# design.net
KiCad netlist of a schematic drawn in EAGLE
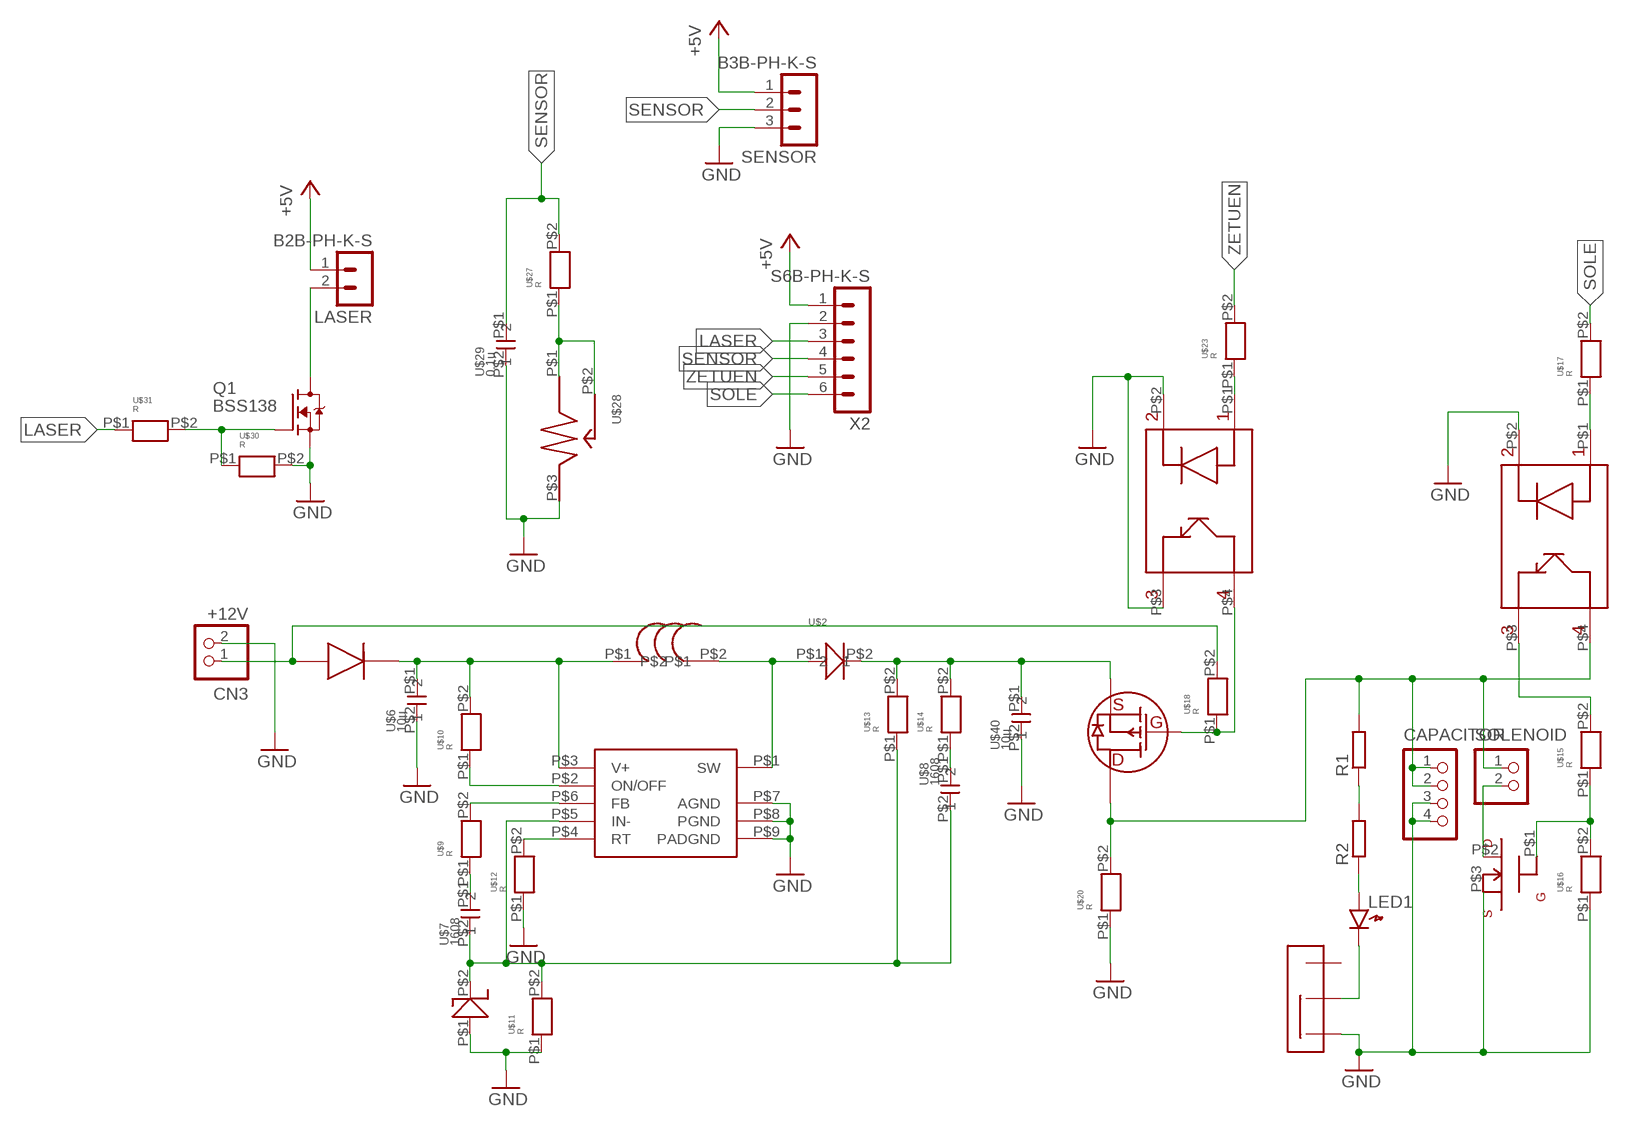
[diagram p0: schematic, sheet 1]
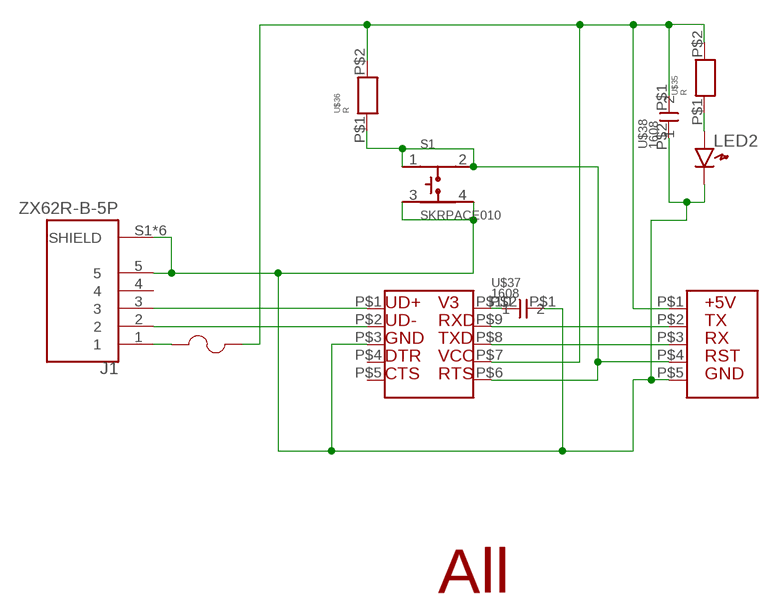
[diagram p1: schematic, sheet 2]

(export (version "E")
  (design (tool "Eeschema 10.0.6"))
  (components
    (comp (ref "CAPACITOR")
      (value "B4B-XH-A")
      (footprint "eagle-import:B4B-XH-A")
      (libsource (lib "eagle-import") (part "B4B-XH-A"))
    )
    (comp (ref "CN3")
      (value "+12V")
      (footprint "eagle-import:B2B-XH-A")
      (libsource (lib "eagle-import") (part "B2B-XH-A"))
    )
    (comp (ref "LASER")
      (value "B2B-PH-K-S")
      (footprint "eagle-import:B2B-PH-K-S")
      (libsource (lib "eagle-import") (part "B2B-PH-K-S"))
    )
    (comp (ref "LED1")
      (value "LED1608")
      (footprint "eagle-import:LED1608")
      (libsource (lib "eagle-import") (part "LED1608"))
    )
    (comp (ref "Q1")
      (value "BSS138")
      (footprint "eagle-import:SOT23")
      (fields (field (name "MF") "Fairchild"))
      (libsource (lib "eagle-import") (part "BSS138"))
    )
    (comp (ref "R1")
      (value "R-EU_0207/10")
      (footprint "eagle-import:0207_10")
      (libsource (lib "eagle-import") (part "R-EU_0207/10"))
    )
    (comp (ref "R2")
      (value "R-EU_0207/10")
      (footprint "eagle-import:0207_10")
      (libsource (lib "eagle-import") (part "R-EU_0207/10"))
    )
    (comp (ref "SENSOR")
      (value "B3B-PH-K-S")
      (footprint "eagle-import:B3B-PH-K-S")
      (libsource (lib "eagle-import") (part "B3B-PH-K-S"))
    )
    (comp (ref "SOLENOID")
      (value "B2B-XH-A")
      (footprint "eagle-import:B2B-XH-A")
      (libsource (lib "eagle-import") (part "B2B-XH-A"))
    )
    (comp (ref "U$1") (value "TD") (footprint "eagle-import:TD") (libsource (lib "eagle-import") (part "TD")))
    (comp (ref "U$2") (value "D") (footprint "eagle-import:D") (libsource (lib "eagle-import") (part "D")))
    (comp (ref "U$3")
      (value "40V5A")
      (footprint "eagle-import:40V5A")
      (libsource (lib "eagle-import") (part "40V5A"))
    )
    (comp (ref "U$4") (value "I") (footprint "eagle-import:I") (libsource (lib "eagle-import") (part "I")))
    (comp (ref "U$5")
      (value "NJW4131GM1")
      (footprint "eagle-import:NJW4131")
      (libsource (lib "eagle-import") (part "NJW4131GM1"))
    )
    (comp (ref "U$6")
      (value "10u")
      (footprint "eagle-import:CON")
      (libsource (lib "eagle-import") (part "1608"))
    )
    (comp (ref "U$7")
      (value "1608")
      (footprint "eagle-import:CON")
      (libsource (lib "eagle-import") (part "1608"))
    )
    (comp (ref "U$8")
      (value "1608")
      (footprint "eagle-import:CON")
      (libsource (lib "eagle-import") (part "1608"))
    )
    (comp (ref "U$9") (value "R") (footprint "eagle-import:1608") (libsource (lib "eagle-import") (part "R")))
    (comp (ref "U$10")
      (value "R")
      (footprint "eagle-import:1608")
      (libsource (lib "eagle-import") (part "R"))
    )
    (comp (ref "U$11")
      (value "R")
      (footprint "eagle-import:1608")
      (libsource (lib "eagle-import") (part "R"))
    )
    (comp (ref "U$12")
      (value "R")
      (footprint "eagle-import:1608")
      (libsource (lib "eagle-import") (part "R"))
    )
    (comp (ref "U$13")
      (value "R")
      (footprint "eagle-import:1608")
      (libsource (lib "eagle-import") (part "R"))
    )
    (comp (ref "U$14")
      (value "R")
      (footprint "eagle-import:1608")
      (libsource (lib "eagle-import") (part "R"))
    )
    (comp (ref "U$15")
      (value "R")
      (footprint "eagle-import:1608")
      (libsource (lib "eagle-import") (part "R"))
    )
    (comp (ref "U$16")
      (value "R")
      (footprint "eagle-import:1608")
      (libsource (lib "eagle-import") (part "R"))
    )
    (comp (ref "U$17")
      (value "R")
      (footprint "eagle-import:1608")
      (libsource (lib "eagle-import") (part "R"))
    )
    (comp (ref "U$18")
      (value "R")
      (footprint "eagle-import:1608")
      (libsource (lib "eagle-import") (part "R"))
    )
    (comp (ref "U$20")
      (value "R")
      (footprint "eagle-import:1608")
      (libsource (lib "eagle-import") (part "R"))
    )
    (comp (ref "U$21")
      (value "MOS")
      (footprint "eagle-import:MOS")
      (libsource (lib "eagle-import") (part "MOS"))
    )
    (comp (ref "U$22")
      (value "PMOSPMOS")
      (footprint "eagle-import:PMOS")
      (libsource (lib "eagle-import") (part "PMOSPMOS"))
    )
    (comp (ref "U$23")
      (value "R")
      (footprint "eagle-import:1608")
      (libsource (lib "eagle-import") (part "R"))
    )
    (comp (ref "U$24")
      (value "TLP291")
      (footprint "eagle-import:TPL291")
      (libsource (lib "eagle-import") (part "TLP291"))
    )
    (comp (ref "U$25")
      (value "TLP291")
      (footprint "eagle-import:TPL291")
      (libsource (lib "eagle-import") (part "TLP291"))
    )
    (comp (ref "U$26")
      (value "SSW")
      (footprint "eagle-import:SSW")
      (libsource (lib "eagle-import") (part "SSW"))
    )
    (comp (ref "U$27")
      (value "R")
      (footprint "eagle-import:1608")
      (libsource (lib "eagle-import") (part "R"))
    )
    (comp (ref "U$28")
      (value "VR")
      (footprint "eagle-import:VR")
      (libsource (lib "eagle-import") (part "VR"))
    )
    (comp (ref "U$29")
      (value "0.1u")
      (footprint "eagle-import:CON")
      (libsource (lib "eagle-import") (part "1608"))
    )
    (comp (ref "U$30")
      (value "R")
      (footprint "eagle-import:1608")
      (libsource (lib "eagle-import") (part "R"))
    )
    (comp (ref "U$31")
      (value "R")
      (footprint "eagle-import:1608")
      (libsource (lib "eagle-import") (part "R"))
    )
    (comp (ref "U$40")
      (value "10u")
      (footprint "eagle-import:CON")
      (libsource (lib "eagle-import") (part "1608"))
    )
    (comp (ref "X2")
      (value "S6B-PH-K-S")
      (footprint "eagle-import:S6B-PH-K-S")
      (libsource (lib "eagle-import") (part "S6B-PH-K-S"))
    )
    (comp (ref "J1")
      (value "ZX62R-B-5P")
      (footprint "eagle-import:HRS_ZX62R-B-5P")
      (fields (field (name "MF") "Hirose"))
      (libsource (lib "eagle-import") (part "ZX62R-B-5P"))
    )
    (comp (ref "LED2")
      (value "LED1608")
      (footprint "eagle-import:LED1608")
      (libsource (lib "eagle-import") (part "LED1608"))
    )
    (comp (ref "S1")
      (value "SKRPACE010")
      (footprint "eagle-import:SW_SKRPACE010")
      (fields (field (name "MF") "ALPS"))
      (libsource (lib "eagle-import") (part "SKRPACE010"))
    )
    (comp (ref "U$32")
      (value "CH340K")
      (footprint "eagle-import:CH340K")
      (libsource (lib "eagle-import") (part "CH340K"))
    )
    (comp (ref "U$33") (value "F") (footprint "eagle-import:F") (libsource (lib "eagle-import") (part "F")))
    (comp (ref "U$34")
      (value "SI")
      (footprint "eagle-import:SI")
      (libsource (lib "eagle-import") (part "SI"))
    )
    (comp (ref "U$35")
      (value "R")
      (footprint "eagle-import:1608")
      (libsource (lib "eagle-import") (part "R"))
    )
    (comp (ref "U$36")
      (value "R")
      (footprint "eagle-import:1608")
      (libsource (lib "eagle-import") (part "R"))
    )
    (comp (ref "U$37")
      (value "1608")
      (footprint "eagle-import:CON")
      (libsource (lib "eagle-import") (part "1608"))
    )
    (comp (ref "U$38")
      (value "1608")
      (footprint "eagle-import:CON")
      (libsource (lib "eagle-import") (part "1608"))
    )
    (comp (ref "U$39")
      (value "ALL")
      (footprint "eagle-import:ALL")
      (libsource (lib "eagle-import") (part "ALL"))
    )
  )
  (nets
    (net (code "1") (name "+5V") (class "Default")
      (node (ref "LASER") (pin "1") (pinfunction "1_1") (pintype "passive"))
      (node (ref "SENSOR") (pin "1") (pinfunction "1_1") (pintype "passive"))
      (node (ref "X2") (pin "1") (pinfunction "1_1") (pintype "passive"))
    )
    (net (code "2") (name "GND") (class "Default")
      (node (ref "CAPACITOR") (pin "3") (pinfunction "3_3") (pintype "passive"))
      (node (ref "CAPACITOR") (pin "4") (pinfunction "4_4") (pintype "passive"))
      (node (ref "CN3") (pin "2") (pinfunction "2_2") (pintype "passive"))
      (node (ref "Q1") (pin "2") (pinfunction "S_2") (pintype "passive"))
      (node (ref "SENSOR") (pin "3") (pinfunction "3_3") (pintype "passive"))
      (node (ref "U$1") (pin "P$1") (pinfunction "P$1_P$1") (pintype "bidirectional"))
      (node (ref "U$11") (pin "P$1") (pinfunction "P$1_P$1") (pintype "bidirectional"))
      (node (ref "U$12") (pin "P$1") (pinfunction "P$1_P$1") (pintype "bidirectional"))
      (node (ref "U$16") (pin "P$1") (pinfunction "P$1_P$1") (pintype "bidirectional"))
      (node (ref "U$20") (pin "P$1") (pinfunction "P$1_P$1") (pintype "bidirectional"))
      (node (ref "U$21") (pin "P$3") (pinfunction "P$2_P$3") (pintype "bidirectional"))
      (node (ref "U$24") (pin "P$2") (pinfunction "2_P$2") (pintype "bidirectional"))
      (node (ref "U$24") (pin "P$3") (pinfunction "3_P$3") (pintype "bidirectional"))
      (node (ref "U$25") (pin "P$2") (pinfunction "2_P$2") (pintype "bidirectional"))
      (node (ref "U$26") (pin "P$1") (pinfunction "P$1_P$1") (pintype "bidirectional"))
      (node (ref "U$28") (pin "P$3") (pinfunction "P$3_P$3") (pintype "bidirectional"))
      (node (ref "U$29") (pin "P$2") (pinfunction "2_P$2") (pintype "bidirectional"))
      (node (ref "U$30") (pin "P$2") (pinfunction "P$2_P$2") (pintype "bidirectional"))
      (node (ref "U$40") (pin "P$2") (pinfunction "2_P$2") (pintype "bidirectional"))
      (node (ref "U$5") (pin "P$7") (pinfunction "AGND_P$7") (pintype "bidirectional"))
      (node (ref "U$5") (pin "P$8") (pinfunction "PGND_P$8") (pintype "bidirectional"))
      (node (ref "U$5") (pin "P$9") (pinfunction "PADGND_P$9") (pintype "bidirectional"))
      (node (ref "U$6") (pin "P$2") (pinfunction "2_P$2") (pintype "bidirectional"))
      (node (ref "X2") (pin "2") (pinfunction "2_2") (pintype "passive"))
    )
    (net (code "3") (name "LASER") (class "Default")
      (node (ref "U$31") (pin "P$1") (pinfunction "P$1_P$1") (pintype "bidirectional"))
      (node (ref "X2") (pin "3") (pinfunction "3_3") (pintype "passive"))
    )
    (net (code "4") (name "Net-(CN3-Pad1)") (class "Default")
      (node (ref "CN3") (pin "1") (pinfunction "1_1") (pintype "passive"))
      (node (ref "U$18") (pin "P$2") (pinfunction "P$2_P$2") (pintype "bidirectional"))
      (node (ref "U$3") (pin "P$1") (pinfunction "P$1_P$1") (pintype "bidirectional"))
    )
    (net (code "5") (name "Net-(J1-Pad1)") (class "Default")
      (node (ref "J1") (pin "1") (pinfunction "1_1") (pintype "passive"))
      (node (ref "U$33") (pin "P$2") (pinfunction "P$2_P$2") (pintype "bidirectional"))
    )
    (net (code "6") (name "Net-(J1-Pad2)") (class "Default")
      (node (ref "J1") (pin "2") (pinfunction "2_2") (pintype "passive"))
      (node (ref "U$32") (pin "P$2") (pinfunction "P$2_P$2") (pintype "bidirectional"))
    )
    (net (code "7") (name "Net-(J1-Pad3)") (class "Default")
      (node (ref "J1") (pin "3") (pinfunction "3_3") (pintype "passive"))
      (node (ref "U$32") (pin "P$1") (pinfunction "P$1_P$1") (pintype "bidirectional"))
    )
    (net (code "8") (name "Net-(LED1-PadA)") (class "Default")
      (node (ref "LED1") (pin "A") (pinfunction "A_A") (pintype "passive"))
      (node (ref "R2") (pin "1") (pinfunction "1_1") (pintype "passive"))
    )
    (net (code "9") (name "Net-(LED2-PadA)") (class "Default")
      (node (ref "LED2") (pin "A") (pinfunction "A_A") (pintype "passive"))
      (node (ref "U$35") (pin "P$1") (pinfunction "P$1_P$1") (pintype "bidirectional"))
    )
    (net (code "10") (name "Net-(Q1-D)") (class "Default")
      (node (ref "LASER") (pin "2") (pinfunction "2_2") (pintype "passive"))
      (node (ref "Q1") (pin "3") (pinfunction "D_3") (pintype "passive"))
    )
    (net (code "11") (name "Net-(Q1-G)") (class "Default")
      (node (ref "Q1") (pin "1") (pinfunction "G_1") (pintype "passive"))
      (node (ref "U$30") (pin "P$1") (pinfunction "P$1_P$1") (pintype "bidirectional"))
      (node (ref "U$31") (pin "P$2") (pinfunction "P$2_P$2") (pintype "bidirectional"))
    )
    (net (code "12") (name "Net-(R1-Pad1)") (class "Default")
      (node (ref "R1") (pin "1") (pinfunction "1_1") (pintype "passive"))
      (node (ref "R2") (pin "2") (pinfunction "2_2") (pintype "passive"))
    )
    (net (code "13") (name "Net-(S1-Pad1)") (class "Default")
      (node (ref "S1") (pin "1") (pinfunction "1_1") (pintype "bidirectional"))
      (node (ref "S1") (pin "2") (pinfunction "2_2") (pintype "bidirectional"))
      (node (ref "U$32") (pin "P$6") (pinfunction "P$6_P$6") (pintype "bidirectional"))
      (node (ref "U$34") (pin "P$4") (pinfunction "P$4_P$4") (pintype "bidirectional"))
      (node (ref "U$36") (pin "P$1") (pinfunction "P$1_P$1") (pintype "bidirectional"))
    )
    (net (code "14") (name "Net-(U$2-1)") (class "Default")
      (node (ref "U$2") (pin "P$1") (pinfunction "1_P$1") (pintype "bidirectional"))
      (node (ref "U$4") (pin "P$2") (pinfunction "P$2_P$2") (pintype "bidirectional"))
      (node (ref "U$5") (pin "P$1") (pinfunction "SW_P$1") (pintype "bidirectional"))
    )
    (net (code "15") (name "Net-(U$2-2)") (class "Default")
      (node (ref "U$13") (pin "P$2") (pinfunction "P$2_P$2") (pintype "bidirectional"))
      (node (ref "U$14") (pin "P$2") (pinfunction "P$2_P$2") (pintype "bidirectional"))
      (node (ref "U$2") (pin "P$2") (pinfunction "2_P$2") (pintype "bidirectional"))
      (node (ref "U$22") (pin "S") (pinfunction "S_S") (pintype "bidirectional"))
      (node (ref "U$40") (pin "P$1") (pinfunction "1_P$1") (pintype "bidirectional"))
    )
    (net (code "16") (name "Net-(U$5-FB)") (class "Default")
      (node (ref "U$5") (pin "P$6") (pinfunction "FB_P$6") (pintype "bidirectional"))
      (node (ref "U$9") (pin "P$2") (pinfunction "P$2_P$2") (pintype "bidirectional"))
    )
    (net (code "17") (name "Net-(U$5-IN-)") (class "Default")
      (node (ref "U$1") (pin "P$2") (pinfunction "P$2_P$2") (pintype "bidirectional"))
      (node (ref "U$11") (pin "P$2") (pinfunction "P$2_P$2") (pintype "bidirectional"))
      (node (ref "U$13") (pin "P$1") (pinfunction "P$1_P$1") (pintype "bidirectional"))
      (node (ref "U$5") (pin "P$5") (pinfunction "IN-_P$5") (pintype "bidirectional"))
      (node (ref "U$7") (pin "P$2") (pinfunction "2_P$2") (pintype "bidirectional"))
      (node (ref "U$8") (pin "P$2") (pinfunction "2_P$2") (pintype "bidirectional"))
    )
    (net (code "18") (name "Net-(U$5-ON{slash}OFF)") (class "Default")
      (node (ref "U$10") (pin "P$1") (pinfunction "P$1_P$1") (pintype "bidirectional"))
      (node (ref "U$5") (pin "P$2") (pinfunction "ON/OFF_P$2") (pintype "bidirectional"))
    )
    (net (code "19") (name "Net-(U$5-RT)") (class "Default")
      (node (ref "U$12") (pin "P$2") (pinfunction "P$2_P$2") (pintype "bidirectional"))
      (node (ref "U$5") (pin "P$4") (pinfunction "RT_P$4") (pintype "bidirectional"))
    )
    (net (code "20") (name "Net-(U$5-V+)") (class "Default")
      (node (ref "U$10") (pin "P$2") (pinfunction "P$2_P$2") (pintype "bidirectional"))
      (node (ref "U$3") (pin "P$2") (pinfunction "P$2_P$2") (pintype "bidirectional"))
      (node (ref "U$4") (pin "P$1") (pinfunction "P$1_P$1") (pintype "bidirectional"))
      (node (ref "U$5") (pin "P$3") (pinfunction "V+_P$3") (pintype "bidirectional"))
      (node (ref "U$6") (pin "P$1") (pinfunction "1_P$1") (pintype "bidirectional"))
    )
    (net (code "21") (name "Net-(U$7-1)") (class "Default")
      (node (ref "U$7") (pin "P$1") (pinfunction "1_P$1") (pintype "bidirectional"))
      (node (ref "U$9") (pin "P$1") (pinfunction "P$1_P$1") (pintype "bidirectional"))
    )
    (net (code "22") (name "Net-(U$8-1)") (class "Default")
      (node (ref "U$14") (pin "P$1") (pinfunction "P$1_P$1") (pintype "bidirectional"))
      (node (ref "U$8") (pin "P$1") (pinfunction "1_P$1") (pintype "bidirectional"))
    )
    (net (code "23") (name "Net-(U$21-P$1)") (class "Default")
      (node (ref "SOLENOID") (pin "2") (pinfunction "2_2") (pintype "passive"))
      (node (ref "U$21") (pin "P$2") (pinfunction "P$1_P$2") (pintype "bidirectional"))
    )
    (net (code "24") (name "Net-(U$21-P$3)") (class "Default")
      (node (ref "U$15") (pin "P$1") (pinfunction "P$1_P$1") (pintype "bidirectional"))
      (node (ref "U$16") (pin "P$2") (pinfunction "P$2_P$2") (pintype "bidirectional"))
      (node (ref "U$21") (pin "P$1") (pinfunction "P$3_P$1") (pintype "bidirectional"))
    )
    (net (code "25") (name "Net-(U$24-1)") (class "Default")
      (node (ref "U$23") (pin "P$1") (pinfunction "P$1_P$1") (pintype "bidirectional"))
      (node (ref "U$24") (pin "P$1") (pinfunction "1_P$1") (pintype "bidirectional"))
    )
    (net (code "26") (name "Net-(U$24-4)") (class "Default")
      (node (ref "U$18") (pin "P$1") (pinfunction "P$1_P$1") (pintype "bidirectional"))
      (node (ref "U$22") (pin "G") (pinfunction "G_G") (pintype "bidirectional"))
      (node (ref "U$24") (pin "P$4") (pinfunction "4_P$4") (pintype "bidirectional"))
    )
    (net (code "27") (name "Net-(U$25-1)") (class "Default")
      (node (ref "U$17") (pin "P$1") (pinfunction "P$1_P$1") (pintype "bidirectional"))
      (node (ref "U$25") (pin "P$1") (pinfunction "1_P$1") (pintype "bidirectional"))
    )
    (net (code "28") (name "Net-(U$25-3)") (class "Default")
      (node (ref "U$15") (pin "P$2") (pinfunction "P$2_P$2") (pintype "bidirectional"))
      (node (ref "U$25") (pin "P$3") (pinfunction "3_P$3") (pintype "bidirectional"))
    )
    (net (code "29") (name "Net-(U$25-4)") (class "Default")
      (node (ref "CAPACITOR") (pin "1") (pinfunction "1_1") (pintype "passive"))
      (node (ref "CAPACITOR") (pin "2") (pinfunction "2_2") (pintype "passive"))
      (node (ref "R1") (pin "2") (pinfunction "2_2") (pintype "passive"))
      (node (ref "SOLENOID") (pin "1") (pinfunction "1_1") (pintype "passive"))
      (node (ref "U$20") (pin "P$2") (pinfunction "P$2_P$2") (pintype "bidirectional"))
      (node (ref "U$22") (pin "D") (pinfunction "D_D") (pintype "bidirectional"))
      (node (ref "U$25") (pin "P$4") (pinfunction "4_P$4") (pintype "bidirectional"))
    )
    (net (code "30") (name "Net-(U$26-P$2)") (class "Default")
      (node (ref "LED1") (pin "K") (pinfunction "K_K") (pintype "passive"))
      (node (ref "U$26") (pin "P$3") (pinfunction "P$2_P$3") (pintype "bidirectional"))
    )
    (net (code "31") (name "Net-(U$27-PadP$1)") (class "Default")
      (node (ref "U$27") (pin "P$1") (pinfunction "P$1_P$1") (pintype "bidirectional"))
      (node (ref "U$28") (pin "P$1") (pinfunction "P$1_P$1") (pintype "bidirectional"))
      (node (ref "U$28") (pin "P$2") (pinfunction "P$2_P$2") (pintype "bidirectional"))
    )
    (net (code "32") (name "Net-(U$32-PadP$8)") (class "Default")
      (node (ref "U$32") (pin "P$8") (pinfunction "P$8_P$8") (pintype "bidirectional"))
      (node (ref "U$34") (pin "P$3") (pinfunction "P$3_P$3") (pintype "bidirectional"))
    )
    (net (code "33") (name "Net-(U$32-PadP$9)") (class "Default")
      (node (ref "U$32") (pin "P$9") (pinfunction "P$9_P$9") (pintype "bidirectional"))
      (node (ref "U$34") (pin "P$2") (pinfunction "P$2_P$2") (pintype "bidirectional"))
    )
    (net (code "34") (name "Net-(U$37-1)") (class "Default")
      (node (ref "J1") (pin "5") (pinfunction "5_5") (pintype "passive"))
      (node (ref "J1") (pin "S1") (pinfunction "SHIELD_S1") (pintype "passive"))
      (node (ref "J1") (pin "S2") (pinfunction "SHIELD_S2") (pintype "passive"))
      (node (ref "J1") (pin "S3") (pinfunction "SHIELD_S3") (pintype "passive"))
      (node (ref "J1") (pin "S4") (pinfunction "SHIELD_S4") (pintype "passive"))
      (node (ref "J1") (pin "S5") (pinfunction "SHIELD_S5") (pintype "passive"))
      (node (ref "J1") (pin "S6") (pinfunction "SHIELD_S6") (pintype "passive"))
      (node (ref "LED2") (pin "K") (pinfunction "K_K") (pintype "passive"))
      (node (ref "S1") (pin "3") (pinfunction "3_3") (pintype "bidirectional"))
      (node (ref "S1") (pin "4") (pinfunction "4_4") (pintype "bidirectional"))
      (node (ref "U$32") (pin "P$3") (pinfunction "P$3_P$3") (pintype "bidirectional"))
      (node (ref "U$34") (pin "P$5") (pinfunction "P$5_P$5") (pintype "bidirectional"))
      (node (ref "U$37") (pin "P$1") (pinfunction "1_P$1") (pintype "bidirectional"))
      (node (ref "U$38") (pin "P$2") (pinfunction "2_P$2") (pintype "bidirectional"))
    )
    (net (code "35") (name "Net-(U$37-2)") (class "Default")
      (node (ref "U$32") (pin "P$10") (pinfunction "P$10_P$10") (pintype "bidirectional"))
      (node (ref "U$37") (pin "P$2") (pinfunction "2_P$2") (pintype "bidirectional"))
    )
    (net (code "36") (name "Net-(U$38-1)") (class "Default")
      (node (ref "U$32") (pin "P$7") (pinfunction "P$7_P$7") (pintype "bidirectional"))
      (node (ref "U$33") (pin "P$1") (pinfunction "P$1_P$1") (pintype "bidirectional"))
      (node (ref "U$34") (pin "P$1") (pinfunction "P$1_P$1") (pintype "bidirectional"))
      (node (ref "U$35") (pin "P$2") (pinfunction "P$2_P$2") (pintype "bidirectional"))
      (node (ref "U$36") (pin "P$2") (pinfunction "P$2_P$2") (pintype "bidirectional"))
      (node (ref "U$38") (pin "P$1") (pinfunction "1_P$1") (pintype "bidirectional"))
    )
    (net (code "37") (name "SENSOR") (class "Default")
      (node (ref "SENSOR") (pin "2") (pinfunction "2_2") (pintype "passive"))
      (node (ref "U$27") (pin "P$2") (pinfunction "P$2_P$2") (pintype "bidirectional"))
      (node (ref "U$29") (pin "P$1") (pinfunction "1_P$1") (pintype "bidirectional"))
      (node (ref "X2") (pin "4") (pinfunction "4_4") (pintype "passive"))
    )
    (net (code "38") (name "SOLE") (class "Default")
      (node (ref "U$17") (pin "P$2") (pinfunction "P$2_P$2") (pintype "bidirectional"))
      (node (ref "X2") (pin "6") (pinfunction "6_6") (pintype "passive"))
    )
    (net (code "39") (name "ZETUEN") (class "Default")
      (node (ref "U$23") (pin "P$2") (pinfunction "P$2_P$2") (pintype "bidirectional"))
      (node (ref "X2") (pin "5") (pinfunction "5_5") (pintype "passive"))
    )
    (net (code "40") (name "unconnected-(J1-Pad4)") (class "Default")
      (node (ref "J1") (pin "4") (pinfunction "4_4") (pintype "passive"))
    )
    (net (code "41") (name "unconnected-(U$26-P$3-PadP$2)") (class "Default")
      (node (ref "U$26") (pin "P$2") (pinfunction "P$3_P$2") (pintype "bidirectional"))
    )
    (net (code "42") (name "unconnected-(U$32-PadP$4)") (class "Default")
      (node (ref "U$32") (pin "P$4") (pinfunction "P$4_P$4") (pintype "bidirectional"))
    )
    (net (code "43") (name "unconnected-(U$32-PadP$5)") (class "Default")
      (node (ref "U$32") (pin "P$5") (pinfunction "P$5_P$5") (pintype "bidirectional"))
    )
  )
)
